# IPF_Remote.net
KiCad netlist of a schematic drawn in EAGLE
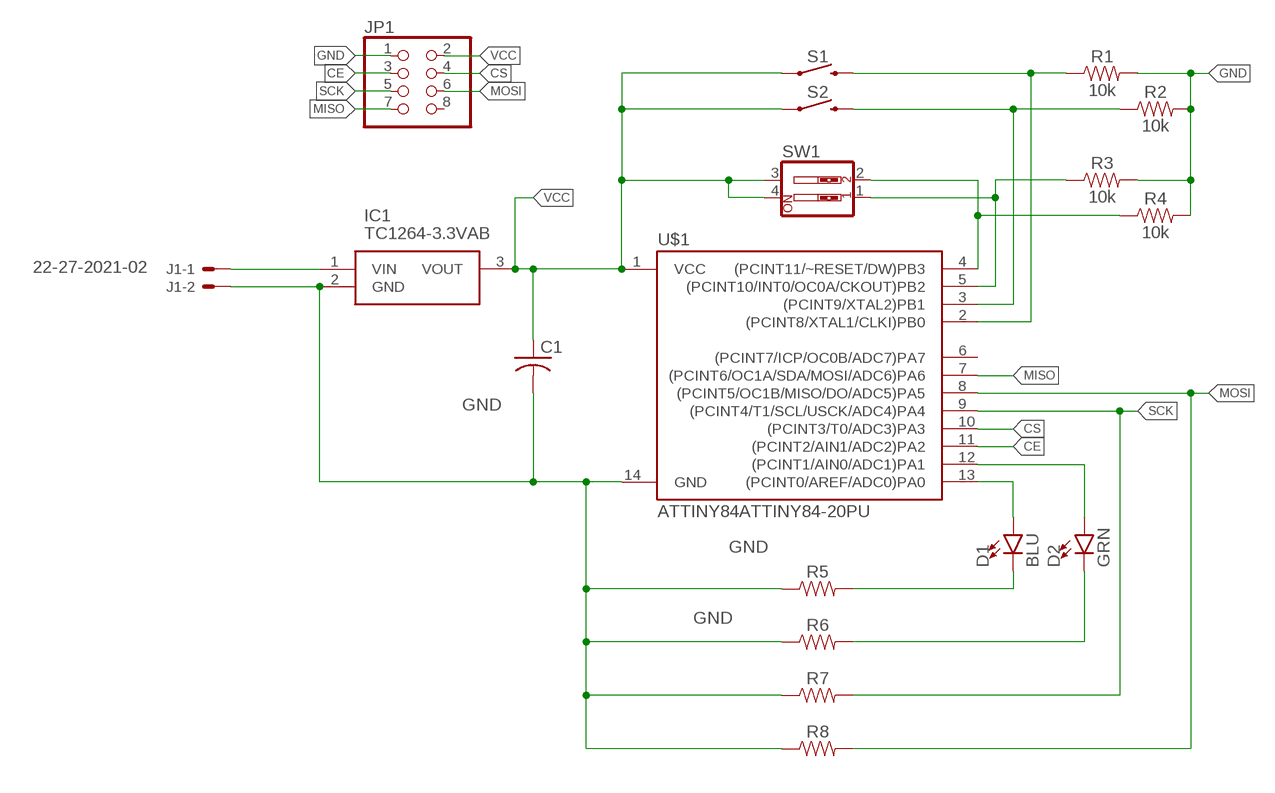
[diagram p0: schematic, sheet 1]

(export (version "E")
  (design (tool "Eeschema 10.0.6"))
  (components
    (comp (ref "C1")
      (value "C-US025-024X044")
      (footprint "eagle-import:C025-024X044")
      (libsource (lib "eagle-import") (part "C-US025-024X044"))
    )
    (comp (ref "D1")
      (value "BLU")
      (footprint "eagle-import:LED_3MM")
      (libsource (lib "eagle-import") (part "LED3MM"))
    )
    (comp (ref "D2")
      (value "GRN")
      (footprint "eagle-import:LED_3MM")
      (libsource (lib "eagle-import") (part "LED3MM"))
    )
    (comp (ref "IC1")
      (value "TC1264-3.3VAB")
      (footprint "eagle-import:TO254P483X988X2222-3P")
      (fields
        (field (name "MOUSER_PART_NUMBER") "579-TC1264-3.3VAB")
        (field (name "RS_PART_NUMBER") "7747655P")
      )
      (libsource (lib "eagle-import") (part "TC1264-3.3VAB"))
    )
    (comp (ref "J1")
      (value "22-27-2021-02")
      (footprint "eagle-import:6410-02")
      (fields (field (name "MF") "MOLEX"))
      (libsource (lib "eagle-import") (part "22-?-0227-2021"))
    )
    (comp (ref "JP1")
      (value "PINHD-2X4")
      (footprint "eagle-import:2X04")
      (libsource (lib "eagle-import") (part "PINHD-2X4"))
    )
    (comp (ref "R1")
      (value "10k")
      (footprint "eagle-import:AXIAL-0.3")
      (libsource (lib "eagle-import") (part "10KOHM-HORIZ-1/4W-1%"))
    )
    (comp (ref "R2")
      (value "10k")
      (footprint "eagle-import:AXIAL-0.3")
      (libsource (lib "eagle-import") (part "10KOHM-HORIZ-1/4W-1%"))
    )
    (comp (ref "R3")
      (value "10k")
      (footprint "eagle-import:AXIAL-0.3")
      (libsource (lib "eagle-import") (part "10KOHM-HORIZ-1/4W-1%"))
    )
    (comp (ref "R4")
      (value "10k")
      (footprint "eagle-import:AXIAL-0.3")
      (libsource (lib "eagle-import") (part "10KOHM-HORIZ-1/4W-1%"))
    )
    (comp (ref "R5")
      (value "RESISTORAXIAL-0.3")
      (footprint "eagle-import:AXIAL-0.3")
      (libsource (lib "eagle-import") (part "RESISTORAXIAL-0.3"))
    )
    (comp (ref "R6")
      (value "RESISTORAXIAL-0.3")
      (footprint "eagle-import:AXIAL-0.3")
      (libsource (lib "eagle-import") (part "RESISTORAXIAL-0.3"))
    )
    (comp (ref "R7")
      (value "RESISTORAXIAL-0.3")
      (footprint "eagle-import:AXIAL-0.3")
      (libsource (lib "eagle-import") (part "RESISTORAXIAL-0.3"))
    )
    (comp (ref "R8")
      (value "RESISTORAXIAL-0.3")
      (footprint "eagle-import:AXIAL-0.3")
      (libsource (lib "eagle-import") (part "RESISTORAXIAL-0.3"))
    )
    (comp (ref "S1")
      (value "MOMENTARY-SWITCH-SPST-PTH-6.0MM")
      (footprint "eagle-import:TACTILE_SWITCH_PTH_6.0MM")
      (libsource (lib "eagle-import") (part "MOMENTARY-SWITCH-SPST-PTH-6.0MM"))
    )
    (comp (ref "S2")
      (value "MOMENTARY-SWITCH-SPST-PTH-6.0MM")
      (footprint "eagle-import:TACTILE_SWITCH_PTH_6.0MM")
      (libsource (lib "eagle-import") (part "MOMENTARY-SWITCH-SPST-PTH-6.0MM"))
    )
    (comp (ref "SW1")
      (value "SW_DIP-2")
      (footprint "eagle-import:EDG-02")
      (libsource (lib "eagle-import") (part "SW_DIP-2"))
    )
    (comp (ref "U$1")
      (value "ATTINY84ATTINY84-20PU")
      (footprint "eagle-import:DIP14")
      (libsource (lib "eagle-import") (part "ATTINY84ATTINY84-20PU"))
    )
  )
  (nets
    (net (code "1") (name "CE") (class "Default")
      (node (ref "JP1") (pin "3") (pinfunction "3_3") (pintype "passive"))
      (node (ref "U$1") (pin "11") (pinfunction "(PCINT2/AIN1/ADC2)PA2_11") (pintype "bidirectional"))
    )
    (net (code "2") (name "CS") (class "Default")
      (node (ref "JP1") (pin "4") (pinfunction "4_4") (pintype "passive"))
      (node (ref "U$1") (pin "10") (pinfunction "(PCINT3/T0/ADC3)PA3_10") (pintype "bidirectional"))
    )
    (net (code "3") (name "GND") (class "Default")
      (node (ref "C1") (pin "2") (pinfunction "2_2") (pintype "passive"))
      (node (ref "IC1") (pin "2") (pinfunction "GND_2") (pintype "bidirectional"))
      (node (ref "J1") (pin "2") (pinfunction "S_2") (pintype "passive"))
      (node (ref "JP1") (pin "1") (pinfunction "1_1") (pintype "passive"))
      (node (ref "R1") (pin "P$2") (pinfunction "2_P$2") (pintype "passive"))
      (node (ref "R2") (pin "P$2") (pinfunction "2_P$2") (pintype "passive"))
      (node (ref "R3") (pin "P$2") (pinfunction "2_P$2") (pintype "passive"))
      (node (ref "R4") (pin "P$2") (pinfunction "2_P$2") (pintype "passive"))
      (node (ref "R5") (pin "P$1") (pinfunction "1_P$1") (pintype "passive"))
      (node (ref "R6") (pin "P$1") (pinfunction "1_P$1") (pintype "passive"))
      (node (ref "R7") (pin "P$1") (pinfunction "1_P$1") (pintype "passive"))
      (node (ref "R8") (pin "P$1") (pinfunction "1_P$1") (pintype "passive"))
      (node (ref "U$1") (pin "14") (pinfunction "GND_14") (pintype "bidirectional"))
    )
    (net (code "4") (name "MISO") (class "Default")
      (node (ref "JP1") (pin "7") (pinfunction "7_7") (pintype "passive"))
      (node (ref "U$1") (pin "7") (pinfunction "(PCINT6/OC1A/SDA/MOSI/ADC6)PA6_7") (pintype "bidirectional"))
    )
    (net (code "5") (name "MOSI") (class "Default")
      (node (ref "JP1") (pin "6") (pinfunction "6_6") (pintype "passive"))
      (node (ref "R8") (pin "P$2") (pinfunction "2_P$2") (pintype "passive"))
      (node (ref "U$1") (pin "8") (pinfunction "(PCINT5/OC1B/MISO/DO/ADC5)PA5_8") (pintype "bidirectional"))
    )
    (net (code "6") (name "Net-(D1-C)") (class "Default")
      (node (ref "D1") (pin "K") (pinfunction "C_K") (pintype "passive"))
      (node (ref "R5") (pin "P$2") (pinfunction "2_P$2") (pintype "passive"))
    )
    (net (code "7") (name "Net-(D2-C)") (class "Default")
      (node (ref "D2") (pin "K") (pinfunction "C_K") (pintype "passive"))
      (node (ref "R6") (pin "P$2") (pinfunction "2_P$2") (pintype "passive"))
    )
    (net (code "8") (name "Net-(IC1-VIN)") (class "Default")
      (node (ref "IC1") (pin "1") (pinfunction "VIN_1") (pintype "bidirectional"))
      (node (ref "J1") (pin "1") (pinfunction "S_1") (pintype "passive"))
    )
    (net (code "9") (name "Net-(R1-1)") (class "Default")
      (node (ref "R1") (pin "P$1") (pinfunction "1_P$1") (pintype "passive"))
      (node (ref "S1") (pin "3") (pinfunction "2_3") (pintype "passive"))
      (node (ref "U$1") (pin "2") (pinfunction "(PCINT8/XTAL1/CLKI)PB0_2") (pintype "bidirectional"))
    )
    (net (code "10") (name "Net-(R2-1)") (class "Default")
      (node (ref "R2") (pin "P$1") (pinfunction "1_P$1") (pintype "passive"))
      (node (ref "S2") (pin "3") (pinfunction "2_3") (pintype "passive"))
      (node (ref "U$1") (pin "3") (pinfunction "(PCINT9/XTAL2)PB1_3") (pintype "bidirectional"))
    )
    (net (code "11") (name "Net-(R3-1)") (class "Default")
      (node (ref "R3") (pin "P$1") (pinfunction "1_P$1") (pintype "passive"))
      (node (ref "SW1") (pin "1") (pinfunction "1_1") (pintype "passive"))
      (node (ref "U$1") (pin "5") (pinfunction "(PCINT10/INT0/OC0A/CKOUT)PB2_5") (pintype "bidirectional"))
    )
    (net (code "12") (name "Net-(R4-1)") (class "Default")
      (node (ref "R4") (pin "P$1") (pinfunction "1_P$1") (pintype "passive"))
      (node (ref "SW1") (pin "2") (pinfunction "2_2") (pintype "passive"))
      (node (ref "U$1") (pin "4") (pinfunction "(PCINT11/~{RESET/DW})PB3_4") (pintype "bidirectional"))
    )
    (net (code "13") (name "Net-(U$1-(PCINT0{slash}AREF{slash}ADC0)PA0)") (class "Default")
      (node (ref "D1") (pin "A") (pinfunction "A_A") (pintype "passive"))
      (node (ref "U$1") (pin "13") (pinfunction "(PCINT0/AREF/ADC0)PA0_13") (pintype "bidirectional"))
    )
    (net (code "14") (name "Net-(U$1-(PCINT1{slash}AIN0{slash}ADC1)PA1)") (class "Default")
      (node (ref "D2") (pin "A") (pinfunction "A_A") (pintype "passive"))
      (node (ref "U$1") (pin "12") (pinfunction "(PCINT1/AIN0/ADC1)PA1_12") (pintype "bidirectional"))
    )
    (net (code "15") (name "SCK") (class "Default")
      (node (ref "JP1") (pin "5") (pinfunction "5_5") (pintype "passive"))
      (node (ref "R7") (pin "P$2") (pinfunction "2_P$2") (pintype "passive"))
      (node (ref "U$1") (pin "9") (pinfunction "(PCINT4/T1/SCL/USCK/ADC4)PA4_9") (pintype "bidirectional"))
    )
    (net (code "16") (name "VCC") (class "Default")
      (node (ref "C1") (pin "1") (pinfunction "1_1") (pintype "passive"))
      (node (ref "IC1") (pin "3") (pinfunction "VOUT_3") (pintype "bidirectional"))
      (node (ref "JP1") (pin "2") (pinfunction "2_2") (pintype "passive"))
      (node (ref "S1") (pin "1") (pinfunction "1_1") (pintype "passive"))
      (node (ref "S2") (pin "1") (pinfunction "1_1") (pintype "passive"))
      (node (ref "SW1") (pin "3") (pinfunction "3_3") (pintype "passive"))
      (node (ref "SW1") (pin "4") (pinfunction "4_4") (pintype "passive"))
      (node (ref "U$1") (pin "1") (pinfunction "VCC_1") (pintype "bidirectional"))
    )
    (net (code "17") (name "unconnected-(JP1-Pad8)") (class "Default")
      (node (ref "JP1") (pin "8") (pinfunction "8_8") (pintype "passive"))
    )
    (net (code "18") (name "unconnected-(U$1-(PCINT7{slash}ICP{slash}OC0B{slash}ADC7)PA7-Pad6)") (class "Default")
      (node (ref "U$1") (pin "6") (pinfunction "(PCINT7/ICP/OC0B/ADC7)PA7_6") (pintype "bidirectional"))
    )
  )
)
